# ADC.net
KiCad netlist of a schematic drawn in Altium Designer
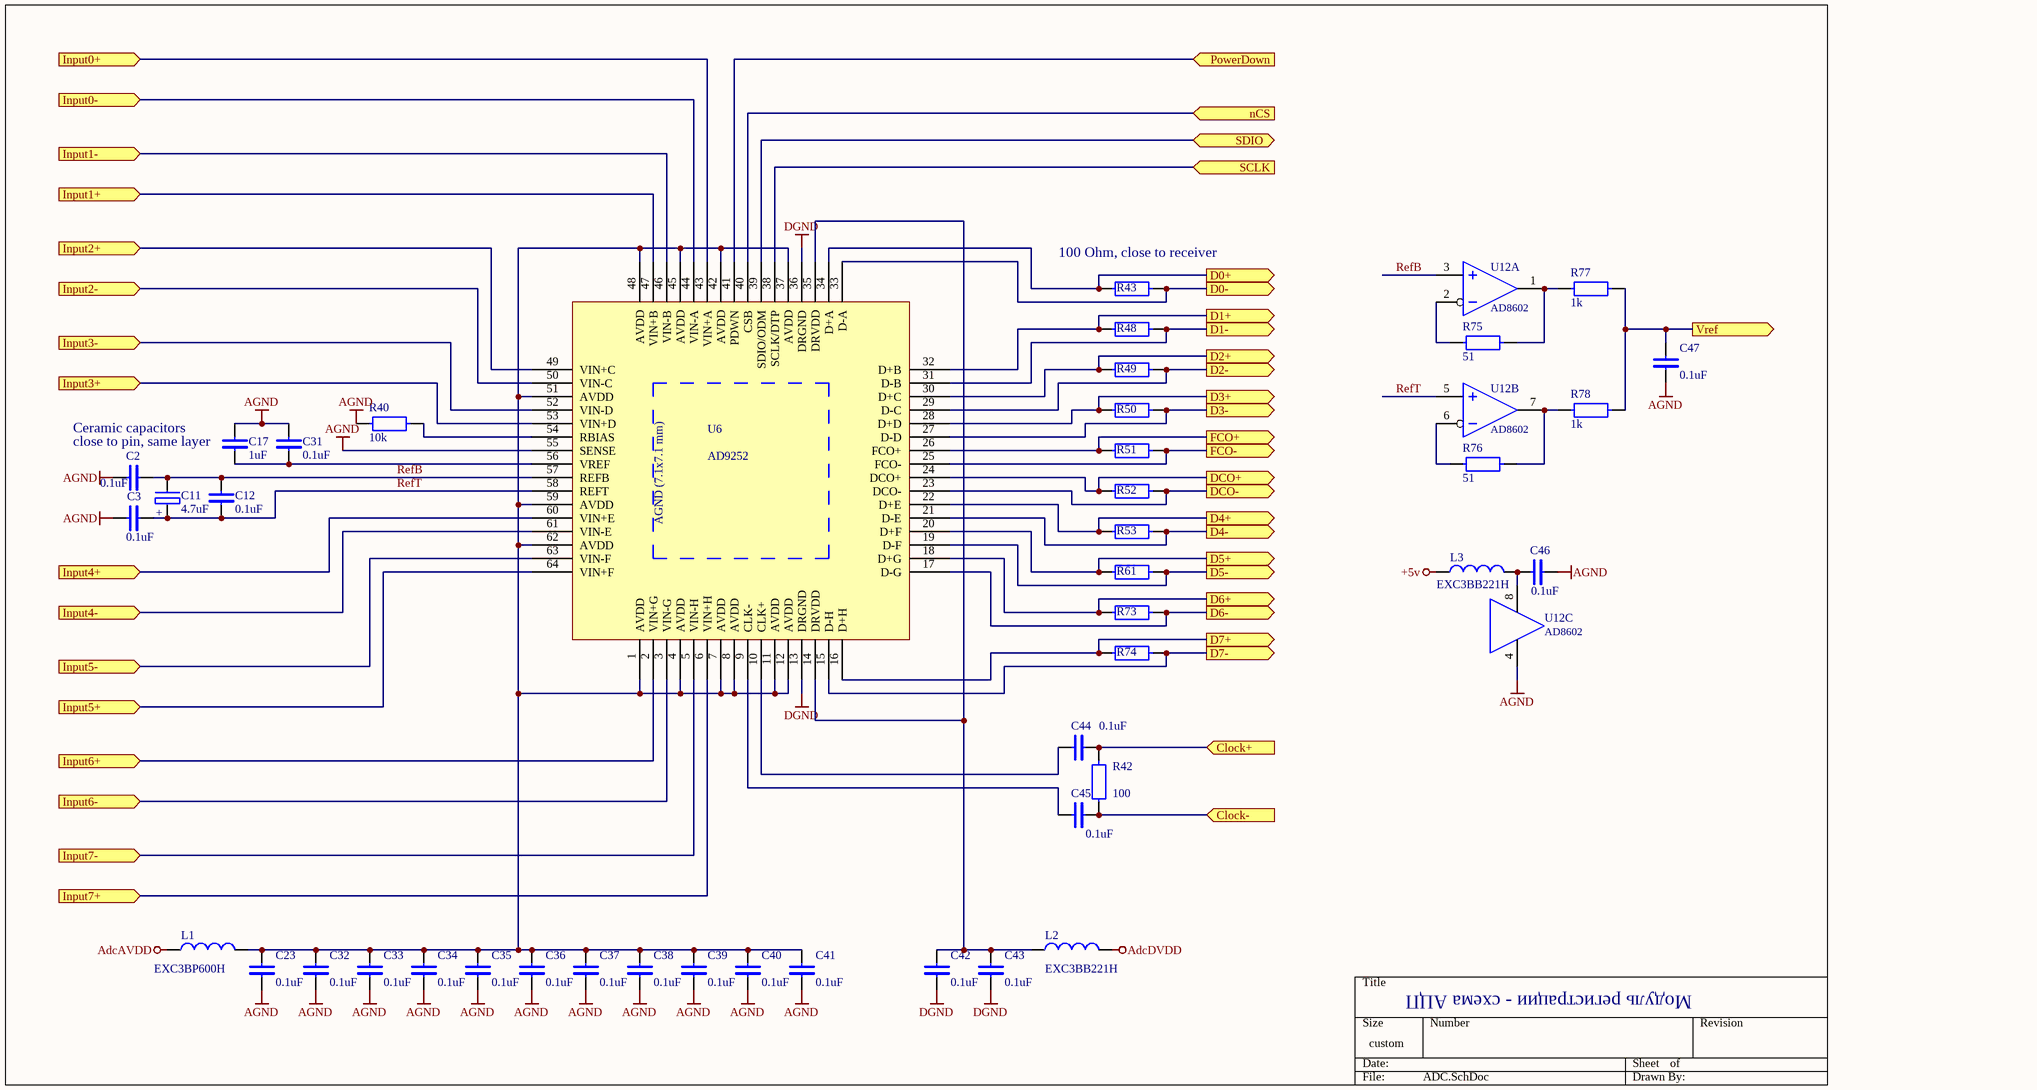
[diagram p0: ADC.SchDoc]

(export (version "E")
  (design (tool "Eeschema 10.0.6"))
  (components
    (comp (ref "C2") (value "0.1uF") (footprint "0402") (libsource (lib "Adevice") (part "c")))
    (comp (ref "C3") (value "0.1uF") (footprint "0402") (libsource (lib "Adevice") (part "c")))
    (comp (ref "C11") (value "4.7uF") (footprint "CP3216") (libsource (lib "Adevice") (part "c+")))
    (comp (ref "C12") (value "0.1uF") (footprint "0402") (libsource (lib "Adevice") (part "c")))
    (comp (ref "C17") (value "1uF") (libsource (lib "Adevice") (part "c")))
    (comp (ref "C23") (value "0.1uF") (footprint "0402") (libsource (lib "Adevice") (part "c")))
    (comp (ref "C31") (value "0.1uF") (footprint "0402") (libsource (lib "Adevice") (part "c")))
    (comp (ref "C32") (value "0.1uF") (footprint "0402") (libsource (lib "Adevice") (part "c")))
    (comp (ref "C33") (value "0.1uF") (footprint "0402") (libsource (lib "Adevice") (part "c")))
    (comp (ref "C34") (value "0.1uF") (footprint "0402") (libsource (lib "Adevice") (part "c")))
    (comp (ref "C35") (value "0.1uF") (footprint "0402") (libsource (lib "Adevice") (part "c")))
    (comp (ref "C36") (value "0.1uF") (footprint "0402") (libsource (lib "Adevice") (part "c")))
    (comp (ref "C37") (value "0.1uF") (footprint "0402") (libsource (lib "Adevice") (part "c")))
    (comp (ref "C38") (value "0.1uF") (footprint "0402") (libsource (lib "Adevice") (part "c")))
    (comp (ref "C39") (value "0.1uF") (footprint "0402") (libsource (lib "Adevice") (part "c")))
    (comp (ref "C40") (value "0.1uF") (footprint "0402") (libsource (lib "Adevice") (part "c")))
    (comp (ref "C41") (value "0.1uF") (footprint "0402") (libsource (lib "Adevice") (part "c")))
    (comp (ref "C42") (value "0.1uF") (footprint "0402") (libsource (lib "Adevice") (part "c")))
    (comp (ref "C43") (value "0.1uF") (footprint "0402") (libsource (lib "Adevice") (part "c")))
    (comp (ref "C44") (value "0.1uF") (footprint "0402") (libsource (lib "Adevice") (part "c")))
    (comp (ref "C45") (value "0.1uF") (footprint "0402") (libsource (lib "Adevice") (part "c")))
    (comp (ref "C46") (value "0.1uF") (footprint "0402") (libsource (lib "Adevice") (part "c")))
    (comp (ref "C47") (value "0.1uF") (footprint "0402") (libsource (lib "Adevice") (part "c")))
    (comp (ref "L1") (value "EXC3BP600H") (footprint "0603") (libsource (lib "Adevice") (part "INDUCTOR")))
    (comp (ref "L2") (value "EXC3BB221H") (footprint "0603") (libsource (lib "Adevice") (part "INDUCTOR")))
    (comp (ref "L3") (value "EXC3BB221H") (footprint "0603") (libsource (lib "Adevice") (part "INDUCTOR")))
    (comp (ref "R40") (value "10k") (footprint "0603") (libsource (lib "Adevice") (part "r")))
    (comp (ref "R42") (value "100") (footprint "0402") (libsource (lib "Adevice") (part "r")))
    (comp (ref "R43") (value "100") (footprint "0402") (libsource (lib "Adevice") (part "r")))
    (comp (ref "R48") (value "100") (footprint "0402") (libsource (lib "Adevice") (part "r")))
    (comp (ref "R49") (value "100") (footprint "0402") (libsource (lib "Adevice") (part "r")))
    (comp (ref "R50") (value "100") (footprint "0402") (libsource (lib "Adevice") (part "r")))
    (comp (ref "R51") (value "100") (footprint "0402") (libsource (lib "Adevice") (part "r")))
    (comp (ref "R52") (value "100") (footprint "0402") (libsource (lib "Adevice") (part "r")))
    (comp (ref "R53") (value "100") (footprint "0402") (libsource (lib "Adevice") (part "r")))
    (comp (ref "R61") (value "100") (footprint "0402") (libsource (lib "Adevice") (part "r")))
    (comp (ref "R73") (value "100") (footprint "0402") (libsource (lib "Adevice") (part "r")))
    (comp (ref "R74") (value "100") (footprint "0402") (libsource (lib "Adevice") (part "r")))
    (comp (ref "R75") (value "51") (footprint "0603") (libsource (lib "Adevice") (part "r")))
    (comp (ref "R76") (value "51") (footprint "0603") (libsource (lib "Adevice") (part "r")))
    (comp (ref "R77") (value "1k") (footprint "0603") (libsource (lib "Adevice") (part "r")))
    (comp (ref "R78") (value "1k") (footprint "0603") (libsource (lib "Adevice") (part "r")))
    (comp (ref "U6")
      (value "AD9252")
      (footprint "CP-64")
      (description "Octal, 14-bit, 50 MSPS, Serial LVDS, 1.8V ADC")
      (libsource (lib "Mylib") (part "AD9252"))
    )
    (comp (ref "U12")
      (value "AD8602")
      (footprint "8SOIC150")
      (description "8 MHz Rail-to-Rail Operational Amplifiers")
      (libsource (lib "Mylib") (part "AD8602"))
    )
  )
  (nets
    (net (code "1") (name "+5v") (class "Default")
      (node (ref "L3") (pin "1") (pinfunction "1_1") (pintype "passive"))
    )
    (net (code "2") (name "/Clock+") (class "Default")
      (node (ref "C44") (pin "1") (pinfunction "1_1") (pintype "passive"))
      (node (ref "R42") (pin "2") (pinfunction "2_2") (pintype "passive"))
    )
    (net (code "3") (name "/Clock-") (class "Default")
      (node (ref "C45") (pin "1") (pinfunction "1_1") (pintype "passive"))
      (node (ref "R42") (pin "1") (pinfunction "1_1") (pintype "passive"))
    )
    (net (code "4") (name "/D0+") (class "Default")
      (node (ref "R43") (pin "1") (pinfunction "1_1") (pintype "passive"))
      (node (ref "U6") (pin "34") (pinfunction "D+A_34") (pintype "passive"))
    )
    (net (code "5") (name "/D0-") (class "Default")
      (node (ref "R43") (pin "2") (pinfunction "2_2") (pintype "passive"))
      (node (ref "U6") (pin "33") (pinfunction "D-A_33") (pintype "passive"))
    )
    (net (code "6") (name "/D1+") (class "Default")
      (node (ref "R48") (pin "1") (pinfunction "1_1") (pintype "passive"))
      (node (ref "U6") (pin "32") (pinfunction "D+B_32") (pintype "passive"))
    )
    (net (code "7") (name "/D1-") (class "Default")
      (node (ref "R48") (pin "2") (pinfunction "2_2") (pintype "passive"))
      (node (ref "U6") (pin "31") (pinfunction "D-B_31") (pintype "passive"))
    )
    (net (code "8") (name "/D2+") (class "Default")
      (node (ref "R49") (pin "1") (pinfunction "1_1") (pintype "passive"))
      (node (ref "U6") (pin "30") (pinfunction "D+C_30") (pintype "passive"))
    )
    (net (code "9") (name "/D2-") (class "Default")
      (node (ref "R49") (pin "2") (pinfunction "2_2") (pintype "passive"))
      (node (ref "U6") (pin "29") (pinfunction "D-C_29") (pintype "passive"))
    )
    (net (code "10") (name "/D3+") (class "Default")
      (node (ref "R50") (pin "1") (pinfunction "1_1") (pintype "passive"))
      (node (ref "U6") (pin "28") (pinfunction "D+D_28") (pintype "passive"))
    )
    (net (code "11") (name "/D3-") (class "Default")
      (node (ref "R50") (pin "2") (pinfunction "2_2") (pintype "passive"))
      (node (ref "U6") (pin "27") (pinfunction "D-D_27") (pintype "passive"))
    )
    (net (code "12") (name "/D4+") (class "Default")
      (node (ref "R53") (pin "1") (pinfunction "1_1") (pintype "passive"))
      (node (ref "U6") (pin "22") (pinfunction "D+E_22") (pintype "passive"))
    )
    (net (code "13") (name "/D4-") (class "Default")
      (node (ref "R53") (pin "2") (pinfunction "2_2") (pintype "passive"))
      (node (ref "U6") (pin "21") (pinfunction "D-E_21") (pintype "passive"))
    )
    (net (code "14") (name "/D5+") (class "Default")
      (node (ref "R61") (pin "1") (pinfunction "1_1") (pintype "passive"))
      (node (ref "U6") (pin "20") (pinfunction "D+F_20") (pintype "passive"))
    )
    (net (code "15") (name "/D5-") (class "Default")
      (node (ref "R61") (pin "2") (pinfunction "2_2") (pintype "passive"))
      (node (ref "U6") (pin "19") (pinfunction "D-F_19") (pintype "passive"))
    )
    (net (code "16") (name "/D6+") (class "Default")
      (node (ref "R73") (pin "1") (pinfunction "1_1") (pintype "passive"))
      (node (ref "U6") (pin "18") (pinfunction "D+G_18") (pintype "passive"))
    )
    (net (code "17") (name "/D6-") (class "Default")
      (node (ref "R73") (pin "2") (pinfunction "2_2") (pintype "passive"))
      (node (ref "U6") (pin "17") (pinfunction "D-G_17") (pintype "passive"))
    )
    (net (code "18") (name "/D7+") (class "Default")
      (node (ref "R74") (pin "1") (pinfunction "1_1") (pintype "passive"))
      (node (ref "U6") (pin "16") (pinfunction "D+H_16") (pintype "passive"))
    )
    (net (code "19") (name "/D7-") (class "Default")
      (node (ref "R74") (pin "2") (pinfunction "2_2") (pintype "passive"))
      (node (ref "U6") (pin "15") (pinfunction "D-H_15") (pintype "passive"))
    )
    (net (code "20") (name "/DCO+") (class "Default")
      (node (ref "R52") (pin "1") (pinfunction "1_1") (pintype "passive"))
      (node (ref "U6") (pin "24") (pinfunction "DCO+_24") (pintype "passive"))
    )
    (net (code "21") (name "/DCO-") (class "Default")
      (node (ref "R52") (pin "2") (pinfunction "2_2") (pintype "passive"))
      (node (ref "U6") (pin "23") (pinfunction "DCO-_23") (pintype "passive"))
    )
    (net (code "22") (name "/FCO+") (class "Default")
      (node (ref "R51") (pin "1") (pinfunction "1_1") (pintype "passive"))
      (node (ref "U6") (pin "26") (pinfunction "FCO+_26") (pintype "passive"))
    )
    (net (code "23") (name "/FCO-") (class "Default")
      (node (ref "R51") (pin "2") (pinfunction "2_2") (pintype "passive"))
      (node (ref "U6") (pin "25") (pinfunction "FCO-_25") (pintype "passive"))
    )
    (net (code "24") (name "/Input0+") (class "Default")
      (node (ref "U6") (pin "43") (pinfunction "VIN+A_43") (pintype "passive"))
    )
    (net (code "25") (name "/Input0-") (class "Default")
      (node (ref "U6") (pin "44") (pinfunction "VIN-A_44") (pintype "passive"))
    )
    (net (code "26") (name "/Input1+") (class "Default")
      (node (ref "U6") (pin "47") (pinfunction "VIN+B_47") (pintype "passive"))
    )
    (net (code "27") (name "/Input1-") (class "Default")
      (node (ref "U6") (pin "46") (pinfunction "VIN-B_46") (pintype "passive"))
    )
    (net (code "28") (name "/Input2+") (class "Default")
      (node (ref "U6") (pin "49") (pinfunction "VIN+C_49") (pintype "passive"))
    )
    (net (code "29") (name "/Input2-") (class "Default")
      (node (ref "U6") (pin "50") (pinfunction "VIN-C_50") (pintype "passive"))
    )
    (net (code "30") (name "/Input3+") (class "Default")
      (node (ref "U6") (pin "53") (pinfunction "VIN+D_53") (pintype "passive"))
    )
    (net (code "31") (name "/Input3-") (class "Default")
      (node (ref "U6") (pin "52") (pinfunction "VIN-D_52") (pintype "passive"))
    )
    (net (code "32") (name "/Input4+") (class "Default")
      (node (ref "U6") (pin "60") (pinfunction "VIN+E_60") (pintype "passive"))
    )
    (net (code "33") (name "/Input4-") (class "Default")
      (node (ref "U6") (pin "61") (pinfunction "VIN-E_61") (pintype "passive"))
    )
    (net (code "34") (name "/Input5+") (class "Default")
      (node (ref "U6") (pin "64") (pinfunction "VIN+F_64") (pintype "passive"))
    )
    (net (code "35") (name "/Input5-") (class "Default")
      (node (ref "U6") (pin "63") (pinfunction "VIN-F_63") (pintype "passive"))
    )
    (net (code "36") (name "/Input6+") (class "Default")
      (node (ref "U6") (pin "2") (pinfunction "VIN+G_2") (pintype "passive"))
    )
    (net (code "37") (name "/Input6-") (class "Default")
      (node (ref "U6") (pin "3") (pinfunction "VIN-G_3") (pintype "passive"))
    )
    (net (code "38") (name "/Input7+") (class "Default")
      (node (ref "U6") (pin "6") (pinfunction "VIN+H_6") (pintype "passive"))
    )
    (net (code "39") (name "/Input7-") (class "Default")
      (node (ref "U6") (pin "5") (pinfunction "VIN-H_5") (pintype "passive"))
    )
    (net (code "40") (name "/PowerDown") (class "Default")
      (node (ref "U6") (pin "41") (pinfunction "PDWN_41") (pintype "passive"))
    )
    (net (code "41") (name "/RefB") (class "Default")
      (node (ref "C11") (pin "-") (pinfunction "-_-") (pintype "passive"))
      (node (ref "C12") (pin "2") (pinfunction "2_2") (pintype "passive"))
      (node (ref "C2") (pin "2") (pinfunction "2_2") (pintype "passive"))
      (node (ref "U12") (pin "3") (pinfunction "IN+_3") (pintype "passive"))
      (node (ref "U6") (pin "57") (pinfunction "REFB_57") (pintype "passive"))
    )
    (net (code "42") (name "/RefT") (class "Default")
      (node (ref "C11") (pin "+") (pinfunction "+_+") (pintype "passive"))
      (node (ref "C12") (pin "1") (pinfunction "1_1") (pintype "passive"))
      (node (ref "C3") (pin "1") (pinfunction "1_1") (pintype "passive"))
      (node (ref "U12") (pin "5") (pinfunction "IN+_5") (pintype "passive"))
      (node (ref "U6") (pin "58") (pinfunction "REFT_58") (pintype "passive"))
    )
    (net (code "43") (name "/SCLK") (class "Default")
      (node (ref "U6") (pin "38") (pinfunction "SCLK/DTP_38") (pintype "passive"))
    )
    (net (code "44") (name "/SDIO") (class "Default")
      (node (ref "U6") (pin "39") (pinfunction "SDIO/ODM_39") (pintype "passive"))
    )
    (net (code "45") (name "/Vref") (class "Default")
      (node (ref "C47") (pin "2") (pinfunction "2_2") (pintype "passive"))
      (node (ref "R77") (pin "2") (pinfunction "2_2") (pintype "passive"))
      (node (ref "R78") (pin "2") (pinfunction "2_2") (pintype "passive"))
    )
    (net (code "46") (name "/nCS") (class "Default")
      (node (ref "U6") (pin "40") (pinfunction "CSB_40") (pintype "passive"))
    )
    (net (code "47") (name "AGND") (class "Default")
      (node (ref "C17") (pin "2") (pinfunction "2_2") (pintype "passive"))
      (node (ref "C2") (pin "1") (pinfunction "1_1") (pintype "passive"))
      (node (ref "C23") (pin "1") (pinfunction "1_1") (pintype "passive"))
      (node (ref "C3") (pin "2") (pinfunction "2_2") (pintype "passive"))
      (node (ref "C31") (pin "2") (pinfunction "2_2") (pintype "passive"))
      (node (ref "C32") (pin "1") (pinfunction "1_1") (pintype "passive"))
      (node (ref "C33") (pin "1") (pinfunction "1_1") (pintype "passive"))
      (node (ref "C34") (pin "1") (pinfunction "1_1") (pintype "passive"))
      (node (ref "C35") (pin "1") (pinfunction "1_1") (pintype "passive"))
      (node (ref "C36") (pin "1") (pinfunction "1_1") (pintype "passive"))
      (node (ref "C37") (pin "1") (pinfunction "1_1") (pintype "passive"))
      (node (ref "C38") (pin "1") (pinfunction "1_1") (pintype "passive"))
      (node (ref "C39") (pin "1") (pinfunction "1_1") (pintype "passive"))
      (node (ref "C40") (pin "1") (pinfunction "1_1") (pintype "passive"))
      (node (ref "C41") (pin "1") (pinfunction "1_1") (pintype "passive"))
      (node (ref "C46") (pin "1") (pinfunction "1_1") (pintype "passive"))
      (node (ref "C47") (pin "1") (pinfunction "1_1") (pintype "passive"))
      (node (ref "R40") (pin "1") (pinfunction "1_1") (pintype "passive"))
      (node (ref "U12") (pin "4") (pinfunction "V-_4") (pintype "passive"))
      (node (ref "U6") (pin "55") (pinfunction "SENSE_55") (pintype "passive"))
    )
    (net (code "48") (name "AdcAVDD") (class "Default")
      (node (ref "L1") (pin "1") (pinfunction "1_1") (pintype "passive"))
    )
    (net (code "49") (name "AdcDVDD") (class "Default")
      (node (ref "L2") (pin "2") (pinfunction "2_2") (pintype "passive"))
    )
    (net (code "50") (name "DGND") (class "Default")
      (node (ref "C42") (pin "1") (pinfunction "1_1") (pintype "passive"))
      (node (ref "C43") (pin "1") (pinfunction "1_1") (pintype "passive"))
      (node (ref "U6") (pin "13") (pinfunction "DRGND_13") (pintype "passive"))
      (node (ref "U6") (pin "36") (pinfunction "DRGND_36") (pintype "passive"))
    )
    (net (code "51") (name "Net-(C23-Pad2)") (class "Default")
      (node (ref "C23") (pin "2") (pinfunction "2_2") (pintype "passive"))
      (node (ref "C32") (pin "2") (pinfunction "2_2") (pintype "passive"))
      (node (ref "C33") (pin "2") (pinfunction "2_2") (pintype "passive"))
      (node (ref "C34") (pin "2") (pinfunction "2_2") (pintype "passive"))
      (node (ref "C35") (pin "2") (pinfunction "2_2") (pintype "passive"))
      (node (ref "C36") (pin "2") (pinfunction "2_2") (pintype "passive"))
      (node (ref "C37") (pin "2") (pinfunction "2_2") (pintype "passive"))
      (node (ref "C38") (pin "2") (pinfunction "2_2") (pintype "passive"))
      (node (ref "C39") (pin "2") (pinfunction "2_2") (pintype "passive"))
      (node (ref "C40") (pin "2") (pinfunction "2_2") (pintype "passive"))
      (node (ref "C41") (pin "2") (pinfunction "2_2") (pintype "passive"))
      (node (ref "L1") (pin "2") (pinfunction "2_2") (pintype "passive"))
      (node (ref "U6") (pin "1") (pinfunction "AVDD_1") (pintype "passive"))
      (node (ref "U6") (pin "11") (pinfunction "AVDD_11") (pintype "passive"))
      (node (ref "U6") (pin "12") (pinfunction "AVDD_12") (pintype "passive"))
      (node (ref "U6") (pin "37") (pinfunction "AVDD_37") (pintype "passive"))
      (node (ref "U6") (pin "4") (pinfunction "AVDD_4") (pintype "passive"))
      (node (ref "U6") (pin "42") (pinfunction "AVDD_42") (pintype "passive"))
      (node (ref "U6") (pin "45") (pinfunction "AVDD_45") (pintype "passive"))
      (node (ref "U6") (pin "48") (pinfunction "AVDD_48") (pintype "passive"))
      (node (ref "U6") (pin "51") (pinfunction "AVDD_51") (pintype "passive"))
      (node (ref "U6") (pin "59") (pinfunction "AVDD_59") (pintype "passive"))
      (node (ref "U6") (pin "62") (pinfunction "AVDD_62") (pintype "passive"))
      (node (ref "U6") (pin "7") (pinfunction "AVDD_7") (pintype "passive"))
      (node (ref "U6") (pin "8") (pinfunction "AVDD_8") (pintype "passive"))
    )
    (net (code "52") (name "Net-(C42-Pad2)") (class "Default")
      (node (ref "C42") (pin "2") (pinfunction "2_2") (pintype "passive"))
      (node (ref "C43") (pin "2") (pinfunction "2_2") (pintype "passive"))
      (node (ref "L2") (pin "1") (pinfunction "1_1") (pintype "passive"))
      (node (ref "U6") (pin "14") (pinfunction "DRVDD_14") (pintype "passive"))
      (node (ref "U6") (pin "35") (pinfunction "DRVDD_35") (pintype "passive"))
    )
    (net (code "53") (name "Net-(U6-CLK+)") (class "Default")
      (node (ref "C44") (pin "2") (pinfunction "2_2") (pintype "passive"))
      (node (ref "U6") (pin "10") (pinfunction "CLK+_10") (pintype "passive"))
    )
    (net (code "54") (name "Net-(U6-CLK-)") (class "Default")
      (node (ref "C45") (pin "2") (pinfunction "2_2") (pintype "passive"))
      (node (ref "U6") (pin "9") (pinfunction "CLK-_9") (pintype "passive"))
    )
    (net (code "55") (name "Net-(U6-RBIAS)") (class "Default")
      (node (ref "R40") (pin "2") (pinfunction "2_2") (pintype "passive"))
      (node (ref "U6") (pin "54") (pinfunction "RBIAS_54") (pintype "passive"))
    )
    (net (code "56") (name "Net-(U6-VREF)") (class "Default")
      (node (ref "C17") (pin "1") (pinfunction "1_1") (pintype "passive"))
      (node (ref "C31") (pin "1") (pinfunction "1_1") (pintype "passive"))
      (node (ref "U6") (pin "56") (pinfunction "VREF_56") (pintype "passive"))
    )
    (net (code "57") (name "Net-(U12A-IN-)") (class "Default")
      (node (ref "R75") (pin "1") (pinfunction "1_1") (pintype "passive"))
      (node (ref "U12") (pin "2") (pinfunction "IN-_2") (pintype "passive"))
    )
    (net (code "58") (name "Net-(U12A-OUT)") (class "Default")
      (node (ref "R75") (pin "2") (pinfunction "2_2") (pintype "passive"))
      (node (ref "R77") (pin "1") (pinfunction "1_1") (pintype "passive"))
      (node (ref "U12") (pin "1") (pinfunction "OUT_1") (pintype "passive"))
    )
    (net (code "59") (name "Net-(U12B-IN-)") (class "Default")
      (node (ref "R76") (pin "1") (pinfunction "1_1") (pintype "passive"))
      (node (ref "U12") (pin "6") (pinfunction "IN-_6") (pintype "passive"))
    )
    (net (code "60") (name "Net-(U12B-OUT)") (class "Default")
      (node (ref "R76") (pin "2") (pinfunction "2_2") (pintype "passive"))
      (node (ref "R78") (pin "1") (pinfunction "1_1") (pintype "passive"))
      (node (ref "U12") (pin "7") (pinfunction "OUT_7") (pintype "passive"))
    )
    (net (code "61") (name "Net-(U12C-V+)") (class "Default")
      (node (ref "C46") (pin "2") (pinfunction "2_2") (pintype "passive"))
      (node (ref "L3") (pin "2") (pinfunction "2_2") (pintype "passive"))
      (node (ref "U12") (pin "8") (pinfunction "V+_8") (pintype "passive"))
    )
  )
)
